# bs_prod.net
KiCad netlist of a schematic drawn in EAGLE
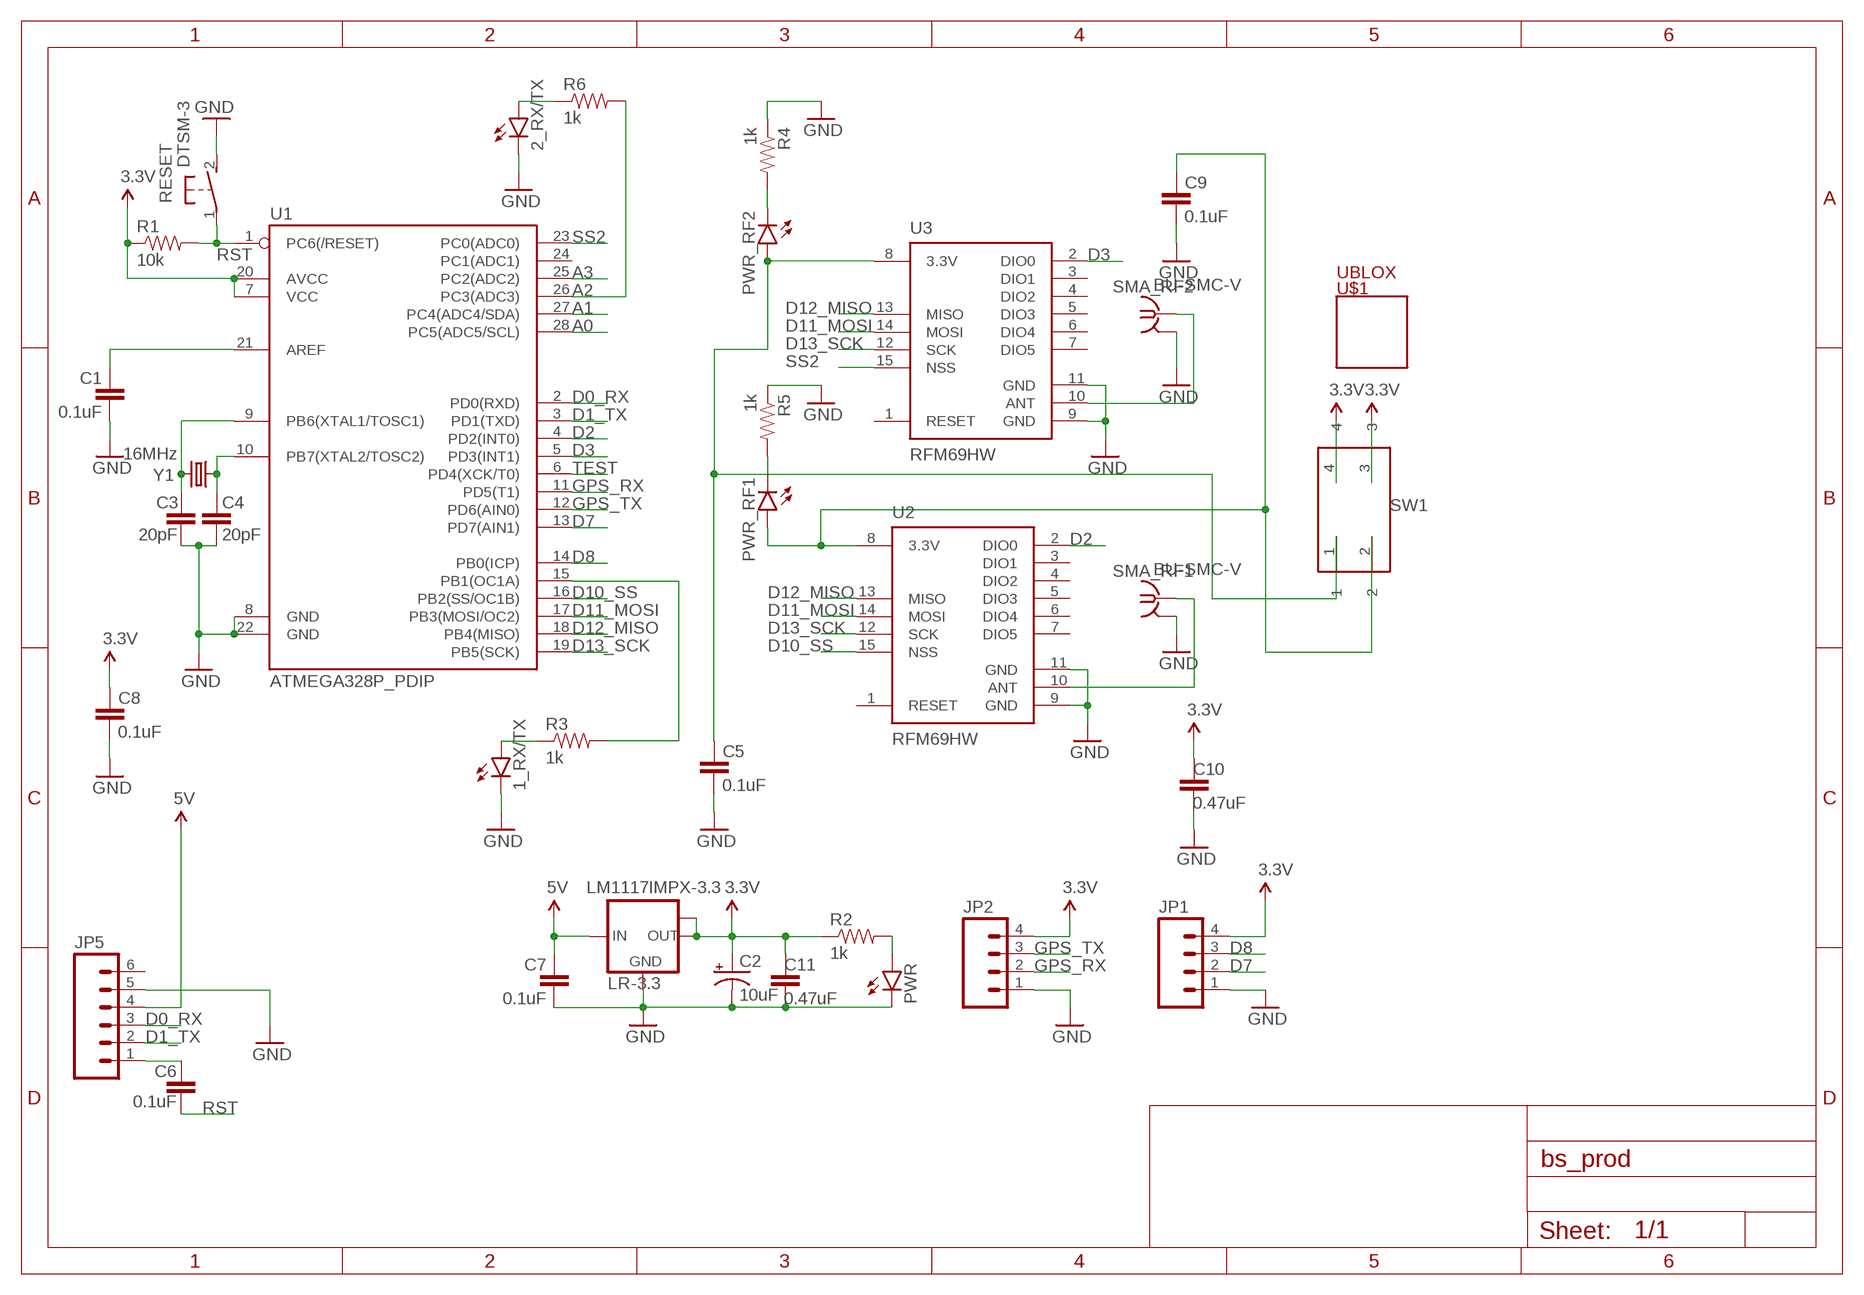
[diagram p0: schematic, sheet 1]

(export (version "E")
  (design (tool "Eeschema 10.0.6"))
  (components
    (comp (ref "1_RX/TX")
      (value "LED1206")
      (footprint "eagle-import:LED-1206")
      (libsource (lib "eagle-import") (part "LED1206"))
    )
    (comp (ref "2_RX/TX")
      (value "LED1206")
      (footprint "eagle-import:LED-1206")
      (libsource (lib "eagle-import") (part "LED1206"))
    )
    (comp (ref "C1")
      (value "0.1uF")
      (footprint "eagle-import:1206")
      (libsource (lib "eagle-import") (part "CAP1206"))
    )
    (comp (ref "C2")
      (value "10uF")
      (footprint "eagle-import:PANASONIC_C")
      (libsource (lib "eagle-import") (part "CAP_POLC"))
    )
    (comp (ref "C3")
      (value "20pF")
      (footprint "eagle-import:1206")
      (libsource (lib "eagle-import") (part "CAP1206"))
    )
    (comp (ref "C4")
      (value "20pF")
      (footprint "eagle-import:1206")
      (libsource (lib "eagle-import") (part "CAP1206"))
    )
    (comp (ref "C5")
      (value "0.1uF")
      (footprint "eagle-import:1206")
      (libsource (lib "eagle-import") (part "CAP1206"))
    )
    (comp (ref "C6")
      (value "0.1uF")
      (footprint "eagle-import:1206")
      (libsource (lib "eagle-import") (part "CAP1206"))
    )
    (comp (ref "C7")
      (value "0.1uF")
      (footprint "eagle-import:1206")
      (libsource (lib "eagle-import") (part "CAP1206"))
    )
    (comp (ref "C8")
      (value "0.1uF")
      (footprint "eagle-import:1206")
      (libsource (lib "eagle-import") (part "CAP1206"))
    )
    (comp (ref "C9")
      (value "0.1uF")
      (footprint "eagle-import:1206")
      (libsource (lib "eagle-import") (part "CAP1206"))
    )
    (comp (ref "C10")
      (value "0.47uF")
      (footprint "eagle-import:1206")
      (libsource (lib "eagle-import") (part "CAP1206"))
    )
    (comp (ref "C11")
      (value "0.47uF")
      (footprint "eagle-import:1206")
      (libsource (lib "eagle-import") (part "CAP1206"))
    )
    (comp (ref "JP1")
      (value "M04PTH")
      (footprint "eagle-import:1X04")
      (libsource (lib "eagle-import") (part "M04PTH"))
    )
    (comp (ref "JP2")
      (value "M04PTH")
      (footprint "eagle-import:1X04")
      (libsource (lib "eagle-import") (part "M04PTH"))
    )
    (comp (ref "JP5")
      (value "M06SIP")
      (footprint "eagle-import:1X06")
      (libsource (lib "eagle-import") (part "M06SIP"))
    )
    (comp (ref "LR-3.3")
      (value "LM1117IMPX-3.3")
      (footprint "eagle-import:SOT223")
      (libsource (lib "eagle-import") (part "LM1117IMPX-3.3"))
    )
    (comp (ref "PWR")
      (value "LED1206")
      (footprint "eagle-import:LED-1206")
      (libsource (lib "eagle-import") (part "LED1206"))
    )
    (comp (ref "PWR_RF1")
      (value "LED1206")
      (footprint "eagle-import:LED-1206")
      (libsource (lib "eagle-import") (part "LED1206"))
    )
    (comp (ref "PWR_RF2")
      (value "LED1206")
      (footprint "eagle-import:LED-1206")
      (libsource (lib "eagle-import") (part "LED1206"))
    )
    (comp (ref "R1")
      (value "10k")
      (footprint "eagle-import:1206")
      (libsource (lib "eagle-import") (part "RESISTOR1206"))
    )
    (comp (ref "R2")
      (value "1k")
      (footprint "eagle-import:1206")
      (libsource (lib "eagle-import") (part "RESISTOR1206"))
    )
    (comp (ref "R3")
      (value "1k")
      (footprint "eagle-import:1206")
      (libsource (lib "eagle-import") (part "RESISTOR1206"))
    )
    (comp (ref "R4")
      (value "1k")
      (footprint "eagle-import:1206")
      (libsource (lib "eagle-import") (part "RESISTOR1206"))
    )
    (comp (ref "R5")
      (value "1k")
      (footprint "eagle-import:1206")
      (libsource (lib "eagle-import") (part "RESISTOR1206"))
    )
    (comp (ref "R6")
      (value "1k")
      (footprint "eagle-import:1206")
      (libsource (lib "eagle-import") (part "RESISTOR1206"))
    )
    (comp (ref "RESET")
      (value "DTSM-3")
      (footprint "eagle-import:DTSM-3")
      (libsource (lib "eagle-import") (part "DTSM-3"))
    )
    (comp (ref "SMA_RF1")
      (value "BU-SMC-V")
      (footprint "eagle-import:BU-SMC-V")
      (libsource (lib "eagle-import") (part "BU-SMC-V"))
    )
    (comp (ref "SMA_RF2")
      (value "BU-SMC-V")
      (footprint "eagle-import:BU-SMC-V")
      (libsource (lib "eagle-import") (part "BU-SMC-V"))
    )
    (comp (ref "SW1")
      (value "418117270902")
      (footprint "eagle-import:418117270902")
      (libsource (lib "eagle-import") (part "418117270902"))
    )
    (comp (ref "U$1")
      (value "UBLOX")
      (footprint "eagle-import:UBLOX")
      (libsource (lib "eagle-import") (part "UBLOX"))
    )
    (comp (ref "U1")
      (value "ATMEGA328P_PDIP")
      (footprint "eagle-import:DIL28-3")
      (libsource (lib "eagle-import") (part "ATMEGA328P_PDIP"))
    )
    (comp (ref "U2")
      (value "RFM69HW")
      (footprint "eagle-import:RFM69W-XXXS2")
      (libsource (lib "eagle-import") (part "RFM69HW"))
    )
    (comp (ref "U3")
      (value "RFM69HW")
      (footprint "eagle-import:RFM69W-XXXS2")
      (libsource (lib "eagle-import") (part "RFM69HW"))
    )
    (comp (ref "Y1")
      (value "16MHz")
      (footprint "eagle-import:HC49UP")
      (libsource (lib "eagle-import") (part "CRYSTALSMD"))
    )
  )
  (nets
    (net (code "1") (name "/A0") (class "Default")
      (node (ref "U1") (pin "28") (pinfunction "PC5(ADC5/SCL)_28") (pintype "bidirectional"))
    )
    (net (code "2") (name "/A1") (class "Default")
      (node (ref "U1") (pin "27") (pinfunction "PC4(ADC4/SDA)_27") (pintype "bidirectional"))
    )
    (net (code "3") (name "/A2") (class "Default")
      (node (ref "R6") (pin "2") (pinfunction "2_2") (pintype "passive"))
      (node (ref "U1") (pin "26") (pinfunction "PC3(ADC3)_26") (pintype "bidirectional"))
    )
    (net (code "4") (name "/A3") (class "Default")
      (node (ref "U1") (pin "25") (pinfunction "PC2(ADC2)_25") (pintype "bidirectional"))
    )
    (net (code "5") (name "/D0_RX") (class "Default")
      (node (ref "JP5") (pin "3") (pinfunction "3_3") (pintype "passive"))
      (node (ref "U1") (pin "2") (pinfunction "PD0(RXD)_2") (pintype "bidirectional"))
    )
    (net (code "6") (name "/D1_TX") (class "Default")
      (node (ref "JP5") (pin "2") (pinfunction "2_2") (pintype "passive"))
      (node (ref "U1") (pin "3") (pinfunction "PD1(TXD)_3") (pintype "bidirectional"))
    )
    (net (code "7") (name "/D2") (class "Default")
      (node (ref "U1") (pin "4") (pinfunction "PD2(INT0)_4") (pintype "bidirectional"))
      (node (ref "U2") (pin "2") (pinfunction "DIO0_2") (pintype "bidirectional"))
    )
    (net (code "8") (name "/D3") (class "Default")
      (node (ref "U1") (pin "5") (pinfunction "PD3(INT1)_5") (pintype "bidirectional"))
      (node (ref "U3") (pin "2") (pinfunction "DIO0_2") (pintype "bidirectional"))
    )
    (net (code "9") (name "/D7") (class "Default")
      (node (ref "JP1") (pin "2") (pinfunction "2_2") (pintype "passive"))
      (node (ref "U1") (pin "13") (pinfunction "PD7(AIN1)_13") (pintype "bidirectional"))
    )
    (net (code "10") (name "/D8") (class "Default")
      (node (ref "JP1") (pin "3") (pinfunction "3_3") (pintype "passive"))
      (node (ref "U1") (pin "14") (pinfunction "PB0(ICP)_14") (pintype "bidirectional"))
    )
    (net (code "11") (name "/D10_SS") (class "Default")
      (node (ref "U1") (pin "16") (pinfunction "PB2(SS/OC1B)_16") (pintype "bidirectional"))
      (node (ref "U2") (pin "15") (pinfunction "NSS_15") (pintype "input"))
    )
    (net (code "12") (name "/D11_MOSI") (class "Default")
      (node (ref "U1") (pin "17") (pinfunction "PB3(MOSI/OC2)_17") (pintype "bidirectional"))
      (node (ref "U2") (pin "14") (pinfunction "MOSI_14") (pintype "input"))
      (node (ref "U3") (pin "14") (pinfunction "MOSI_14") (pintype "input"))
    )
    (net (code "13") (name "/D12_MISO") (class "Default")
      (node (ref "U1") (pin "18") (pinfunction "PB4(MISO)_18") (pintype "bidirectional"))
      (node (ref "U2") (pin "13") (pinfunction "MISO_13") (pintype "bidirectional"))
      (node (ref "U3") (pin "13") (pinfunction "MISO_13") (pintype "bidirectional"))
    )
    (net (code "14") (name "/D13_SCK") (class "Default")
      (node (ref "U1") (pin "19") (pinfunction "PB5(SCK)_19") (pintype "bidirectional"))
      (node (ref "U2") (pin "12") (pinfunction "SCK_12") (pintype "input"))
      (node (ref "U3") (pin "12") (pinfunction "SCK_12") (pintype "input"))
    )
    (net (code "15") (name "/GPS_RX") (class "Default")
      (node (ref "JP2") (pin "2") (pinfunction "2_2") (pintype "passive"))
      (node (ref "U1") (pin "11") (pinfunction "PD5(T1)_11") (pintype "bidirectional"))
    )
    (net (code "16") (name "/GPS_TX") (class "Default")
      (node (ref "JP2") (pin "3") (pinfunction "3_3") (pintype "passive"))
      (node (ref "U1") (pin "12") (pinfunction "PD6(AIN0)_12") (pintype "bidirectional"))
    )
    (net (code "17") (name "/RST") (class "Default")
      (node (ref "C6") (pin "2") (pinfunction "2_2") (pintype "passive"))
      (node (ref "R1") (pin "2") (pinfunction "2_2") (pintype "passive"))
      (node (ref "RESET") (pin "1") (pinfunction "1_1") (pintype "passive"))
      (node (ref "U1") (pin "1") (pinfunction "PC6(/RESET)_1") (pintype "bidirectional"))
    )
    (net (code "18") (name "/SS2") (class "Default")
      (node (ref "U1") (pin "23") (pinfunction "PC0(ADC0)_23") (pintype "bidirectional"))
      (node (ref "U3") (pin "15") (pinfunction "NSS_15") (pintype "input"))
    )
    (net (code "19") (name "/TEST") (class "Default")
      (node (ref "U1") (pin "6") (pinfunction "PD4(XCK/T0)_6") (pintype "bidirectional"))
    )
    (net (code "20") (name "3.3V") (class "Default")
      (node (ref "C10") (pin "1") (pinfunction "1_1") (pintype "passive"))
      (node (ref "C11") (pin "1") (pinfunction "1_1") (pintype "passive"))
      (node (ref "C2") (pin "+") (pinfunction "+_+") (pintype "passive"))
      (node (ref "C8") (pin "1") (pinfunction "1_1") (pintype "passive"))
      (node (ref "JP1") (pin "4") (pinfunction "4_4") (pintype "passive"))
      (node (ref "JP2") (pin "4") (pinfunction "4_4") (pintype "passive"))
      (node (ref "LR-3.3") (pin "2") (pinfunction "OUT_2") (pintype "passive"))
      (node (ref "LR-3.3") (pin "TAB") (pinfunction "OUT1_TAB") (pintype "passive"))
      (node (ref "R1") (pin "1") (pinfunction "1_1") (pintype "passive"))
      (node (ref "R2") (pin "1") (pinfunction "1_1") (pintype "passive"))
      (node (ref "SW1") (pin "3") (pinfunction "3_3") (pintype "bidirectional"))
      (node (ref "SW1") (pin "4") (pinfunction "4_4") (pintype "bidirectional"))
      (node (ref "U1") (pin "20") (pinfunction "AVCC_20") (pintype "bidirectional"))
      (node (ref "U1") (pin "7") (pinfunction "VCC_7") (pintype "bidirectional"))
    )
    (net (code "21") (name "5V") (class "Default")
      (node (ref "C7") (pin "1") (pinfunction "1_1") (pintype "passive"))
      (node (ref "JP5") (pin "4") (pinfunction "4_4") (pintype "passive"))
      (node (ref "LR-3.3") (pin "3") (pinfunction "IN_3") (pintype "input"))
    )
    (net (code "22") (name "GND") (class "Default")
      (node (ref "1_RX/TX") (pin "C") (pinfunction "C_C") (pintype "passive"))
      (node (ref "2_RX/TX") (pin "C") (pinfunction "C_C") (pintype "passive"))
      (node (ref "C1") (pin "2") (pinfunction "2_2") (pintype "passive"))
      (node (ref "C10") (pin "2") (pinfunction "2_2") (pintype "passive"))
      (node (ref "C11") (pin "2") (pinfunction "2_2") (pintype "passive"))
      (node (ref "C2") (pin "-") (pinfunction "-_-") (pintype "passive"))
      (node (ref "C3") (pin "2") (pinfunction "2_2") (pintype "passive"))
      (node (ref "C4") (pin "2") (pinfunction "2_2") (pintype "passive"))
      (node (ref "C5") (pin "2") (pinfunction "2_2") (pintype "passive"))
      (node (ref "C7") (pin "2") (pinfunction "2_2") (pintype "passive"))
      (node (ref "C8") (pin "2") (pinfunction "2_2") (pintype "passive"))
      (node (ref "C9") (pin "2") (pinfunction "2_2") (pintype "passive"))
      (node (ref "JP1") (pin "1") (pinfunction "1_1") (pintype "passive"))
      (node (ref "JP2") (pin "1") (pinfunction "1_1") (pintype "passive"))
      (node (ref "JP5") (pin "5") (pinfunction "5_5") (pintype "passive"))
      (node (ref "LR-3.3") (pin "1") (pinfunction "GND_1") (pintype "input"))
      (node (ref "PWR") (pin "C") (pinfunction "C_C") (pintype "passive"))
      (node (ref "R4") (pin "1") (pinfunction "1_1") (pintype "passive"))
      (node (ref "R5") (pin "1") (pinfunction "1_1") (pintype "passive"))
      (node (ref "RESET") (pin "2") (pinfunction "2_2") (pintype "passive"))
      (node (ref "SMA_RF1") (pin "2") (pinfunction "2_2") (pintype "passive"))
      (node (ref "SMA_RF1") (pin "3") (pinfunction "2_3") (pintype "passive"))
      (node (ref "SMA_RF1") (pin "4") (pinfunction "2_4") (pintype "passive"))
      (node (ref "SMA_RF1") (pin "5") (pinfunction "2_5") (pintype "passive"))
      (node (ref "SMA_RF2") (pin "2") (pinfunction "2_2") (pintype "passive"))
      (node (ref "SMA_RF2") (pin "3") (pinfunction "2_3") (pintype "passive"))
      (node (ref "SMA_RF2") (pin "4") (pinfunction "2_4") (pintype "passive"))
      (node (ref "SMA_RF2") (pin "5") (pinfunction "2_5") (pintype "passive"))
      (node (ref "U1") (pin "22") (pinfunction "GND_22") (pintype "bidirectional"))
      (node (ref "U1") (pin "8") (pinfunction "GND_8") (pintype "bidirectional"))
      (node (ref "U2") (pin "11") (pinfunction "GND_11") (pintype "power_in"))
      (node (ref "U2") (pin "9") (pinfunction "GND_9") (pintype "power_in"))
      (node (ref "U3") (pin "11") (pinfunction "GND_11") (pintype "power_in"))
      (node (ref "U3") (pin "9") (pinfunction "GND_9") (pintype "power_in"))
    )
    (net (code "23") (name "Net-(1_RX/TX-PadA)") (class "Default")
      (node (ref "1_RX/TX") (pin "A") (pinfunction "A_A") (pintype "passive"))
      (node (ref "R3") (pin "1") (pinfunction "1_1") (pintype "passive"))
    )
    (net (code "24") (name "Net-(2_RX/TX-PadA)") (class "Default")
      (node (ref "2_RX/TX") (pin "A") (pinfunction "A_A") (pintype "passive"))
      (node (ref "R6") (pin "1") (pinfunction "1_1") (pintype "passive"))
    )
    (net (code "25") (name "Net-(C6-Pad1)") (class "Default")
      (node (ref "C6") (pin "1") (pinfunction "1_1") (pintype "passive"))
      (node (ref "JP5") (pin "1") (pinfunction "1_1") (pintype "passive"))
    )
    (net (code "26") (name "Net-(PWR-PadA)") (class "Default")
      (node (ref "PWR") (pin "A") (pinfunction "A_A") (pintype "passive"))
      (node (ref "R2") (pin "2") (pinfunction "2_2") (pintype "passive"))
    )
    (net (code "27") (name "Net-(PWR_RF1-PadC)") (class "Default")
      (node (ref "PWR_RF1") (pin "C") (pinfunction "C_C") (pintype "passive"))
      (node (ref "R5") (pin "2") (pinfunction "2_2") (pintype "passive"))
    )
    (net (code "28") (name "Net-(PWR_RF2-PadC)") (class "Default")
      (node (ref "PWR_RF2") (pin "C") (pinfunction "C_C") (pintype "passive"))
      (node (ref "R4") (pin "2") (pinfunction "2_2") (pintype "passive"))
    )
    (net (code "29") (name "Net-(U1-AREF)") (class "Default")
      (node (ref "C1") (pin "1") (pinfunction "1_1") (pintype "passive"))
      (node (ref "U1") (pin "21") (pinfunction "AREF_21") (pintype "bidirectional"))
    )
    (net (code "30") (name "Net-(U1-PB1(OC1A))") (class "Default")
      (node (ref "R3") (pin "2") (pinfunction "2_2") (pintype "passive"))
      (node (ref "U1") (pin "15") (pinfunction "PB1(OC1A)_15") (pintype "bidirectional"))
    )
    (net (code "31") (name "Net-(U1-PB6(XTAL1{slash}TOSC1))") (class "Default")
      (node (ref "C3") (pin "1") (pinfunction "1_1") (pintype "passive"))
      (node (ref "U1") (pin "9") (pinfunction "PB6(XTAL1/TOSC1)_9") (pintype "bidirectional"))
      (node (ref "Y1") (pin "2") (pinfunction "2_2") (pintype "passive"))
    )
    (net (code "32") (name "Net-(U1-PB7(XTAL2{slash}TOSC2))") (class "Default")
      (node (ref "C4") (pin "1") (pinfunction "1_1") (pintype "passive"))
      (node (ref "U1") (pin "10") (pinfunction "PB7(XTAL2/TOSC2)_10") (pintype "bidirectional"))
      (node (ref "Y1") (pin "1") (pinfunction "1_1") (pintype "passive"))
    )
    (net (code "33") (name "Net-(U2-3.3V)") (class "Default")
      (node (ref "C9") (pin "1") (pinfunction "1_1") (pintype "passive"))
      (node (ref "PWR_RF1") (pin "A") (pinfunction "A_A") (pintype "passive"))
      (node (ref "SW1") (pin "2") (pinfunction "2_2") (pintype "bidirectional"))
      (node (ref "U2") (pin "8") (pinfunction "3.3V_8") (pintype "power_in"))
    )
    (net (code "34") (name "Net-(U2-ANT)") (class "Default")
      (node (ref "SMA_RF1") (pin "1") (pinfunction "1_1") (pintype "passive"))
      (node (ref "U2") (pin "10") (pinfunction "ANT_10") (pintype "passive"))
    )
    (net (code "35") (name "Net-(U3-3.3V)") (class "Default")
      (node (ref "C5") (pin "1") (pinfunction "1_1") (pintype "passive"))
      (node (ref "PWR_RF2") (pin "A") (pinfunction "A_A") (pintype "passive"))
      (node (ref "SW1") (pin "1") (pinfunction "1_1") (pintype "bidirectional"))
      (node (ref "U3") (pin "8") (pinfunction "3.3V_8") (pintype "power_in"))
    )
    (net (code "36") (name "Net-(U3-ANT)") (class "Default")
      (node (ref "SMA_RF2") (pin "1") (pinfunction "1_1") (pintype "passive"))
      (node (ref "U3") (pin "10") (pinfunction "ANT_10") (pintype "passive"))
    )
    (net (code "37") (name "unconnected-(JP5-Pad6)") (class "Default")
      (node (ref "JP5") (pin "6") (pinfunction "6_6") (pintype "passive"))
    )
    (net (code "38") (name "unconnected-(U1-PC1(ADC1)-Pad24)") (class "Default")
      (node (ref "U1") (pin "24") (pinfunction "PC1(ADC1)_24") (pintype "bidirectional"))
    )
    (net (code "39") (name "unconnected-(U2-DIO1-Pad3)") (class "Default")
      (node (ref "U2") (pin "3") (pinfunction "DIO1_3") (pintype "bidirectional"))
    )
    (net (code "40") (name "unconnected-(U2-DIO2-Pad4)") (class "Default")
      (node (ref "U2") (pin "4") (pinfunction "DIO2_4") (pintype "bidirectional"))
    )
    (net (code "41") (name "unconnected-(U2-DIO3-Pad5)") (class "Default")
      (node (ref "U2") (pin "5") (pinfunction "DIO3_5") (pintype "bidirectional"))
    )
    (net (code "42") (name "unconnected-(U2-DIO4-Pad6)") (class "Default")
      (node (ref "U2") (pin "6") (pinfunction "DIO4_6") (pintype "bidirectional"))
    )
    (net (code "43") (name "unconnected-(U2-DIO5-Pad7)") (class "Default")
      (node (ref "U2") (pin "7") (pinfunction "DIO5_7") (pintype "bidirectional"))
    )
    (net (code "44") (name "unconnected-(U2-RESET-Pad1)") (class "Default")
      (node (ref "U2") (pin "1") (pinfunction "RESET_1") (pintype "input"))
    )
    (net (code "45") (name "unconnected-(U3-DIO1-Pad3)") (class "Default")
      (node (ref "U3") (pin "3") (pinfunction "DIO1_3") (pintype "bidirectional"))
    )
    (net (code "46") (name "unconnected-(U3-DIO2-Pad4)") (class "Default")
      (node (ref "U3") (pin "4") (pinfunction "DIO2_4") (pintype "bidirectional"))
    )
    (net (code "47") (name "unconnected-(U3-DIO3-Pad5)") (class "Default")
      (node (ref "U3") (pin "5") (pinfunction "DIO3_5") (pintype "bidirectional"))
    )
    (net (code "48") (name "unconnected-(U3-DIO4-Pad6)") (class "Default")
      (node (ref "U3") (pin "6") (pinfunction "DIO4_6") (pintype "bidirectional"))
    )
    (net (code "49") (name "unconnected-(U3-DIO5-Pad7)") (class "Default")
      (node (ref "U3") (pin "7") (pinfunction "DIO5_7") (pintype "bidirectional"))
    )
    (net (code "50") (name "unconnected-(U3-RESET-Pad1)") (class "Default")
      (node (ref "U3") (pin "1") (pinfunction "RESET_1") (pintype "input"))
    )
  )
)
